# MAX490.net
KiCad netlist of a schematic drawn in Altium Designer
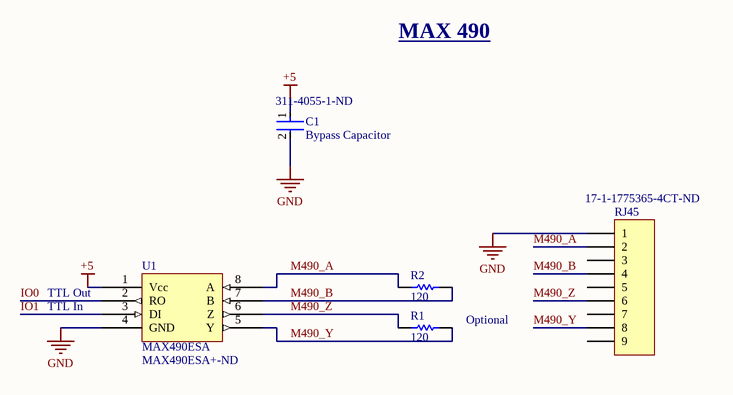
[diagram p0: MAX490.SchDoc]

(export (version "E")
  (design (tool "Eeschema 10.0.6"))
  (components
    (comp (ref "C1")
      (value "Bypass Capacitor")
      (footprint "FP-CC0603-DA-MFG")
      (description "CAP CER 0.1UF 10V X7R 0603")
      (fields
        (field (name "OCTOPART") "https://octopart.com/cc0603krx7r6bb104-yageo-9291607")
        (field (name "TOLERANCE") "0.1")
        (field (name "SUPPLIER PART NUMBER 1") "311-4055-1-ND")
      )
      (libsource (lib "Altium Content Vault") (part "11868f565c42a9108669ba33697ecf6"))
    )
    (comp (ref "R1")
      (value "Optional")
      (footprint "1608[0603]")
      (description "SMD Chip Resistor, 120 Ohm, ± 5%, 250 mW, 0603 [1608 Metric], Thick Film, Anti-Surge")
      (fields
        (field (name "ALTIUM_VALUE") "120")
        (field (name "MANUFACTURER") "Panasonic")
        (field (name "MANUFACTURER PART NUMBER") "ERJ-PA3J121V")
      )
      (libsource (lib "Miscellaneous Devices") (part "Res1"))
    )
    (comp (ref "R2")
      (value "120")
      (footprint "1608[0603]")
      (description "SMD Chip Resistor, 120 Ohm, ± 5%, 250 mW, 0603 [1608 Metric], Thick Film, Anti-Surge")
      (fields
        (field (name "MANUFACTURER") "Panasonic")
        (field (name "MANUFACTURER PART NUMBER") "ERJ-PA3J121V")
      )
      (libsource (lib "Miscellaneous Devices") (part "Res1"))
    )
    (comp (ref "RJ45")
      (value "~")
      (footprint "1-1775365-4")
      (description "Telecom and Datacom Connector")
      (fields
        (field (name "SUPPLIER PART NUMBER 1") "17-1-1775365-4CT-ND")
        (field (name "MANUFACTURER") "TE Connectivity AMP")
        (field (name "MANUFACTURER PART NUMBER") "1-1775365-4")
      )
      (libsource (lib "Miscellaneous Connectors") (part "Header 9"))
    )
    (comp (ref "U1")
      (value "MAX490ESA")
      (footprint "SO-8_L")
      (description "Line Transceiver, 1 Func, 1 Driver, 1 Rcvr, CMOS, PDSO8")
      (fields
        (field (name "MANUFACTURER") "Maxim")
        (field (name "MANUFACTURER PART NUMBER") "MAX490ESA+")
        (field (name "SUPPLIER PART NUMBER 1") "MAX490ESA+-ND")
      )
      (libsource (lib "MAX490_Corrected_Symbol") (part "MAX490ESA"))
    )
  )
  (nets
    (net (code "1") (name "+5") (class "Default")
      (node (ref "C1") (pin "1") (pinfunction "1_1") (pintype "passive"))
      (node (ref "U1") (pin "1") (pinfunction "Vcc_1") (pintype "power_in"))
    )
    (net (code "2") (name "/IO0") (class "Default")
      (node (ref "U1") (pin "2") (pinfunction "RO_2") (pintype "output"))
    )
    (net (code "3") (name "/IO1") (class "Default")
      (node (ref "U1") (pin "3") (pinfunction "DI_3") (pintype "input"))
    )
    (net (code "4") (name "/M490_A") (class "Default")
      (node (ref "R2") (pin "2") (pinfunction "2_2") (pintype "passive"))
      (node (ref "RJ45") (pin "2") (pinfunction "2_2") (pintype "passive"))
      (node (ref "U1") (pin "8") (pinfunction "A_8") (pintype "input"))
    )
    (net (code "5") (name "/M490_B") (class "Default")
      (node (ref "R2") (pin "1") (pinfunction "1_1") (pintype "passive"))
      (node (ref "RJ45") (pin "4") (pinfunction "4_4") (pintype "passive"))
      (node (ref "U1") (pin "7") (pinfunction "B_7") (pintype "input"))
    )
    (net (code "6") (name "/M490_Y") (class "Default")
      (node (ref "R1") (pin "1") (pinfunction "1_1") (pintype "passive"))
      (node (ref "RJ45") (pin "8") (pinfunction "8_8") (pintype "passive"))
      (node (ref "U1") (pin "5") (pinfunction "Y_5") (pintype "output"))
    )
    (net (code "7") (name "/M490_Z") (class "Default")
      (node (ref "R1") (pin "2") (pinfunction "2_2") (pintype "passive"))
      (node (ref "RJ45") (pin "6") (pinfunction "6_6") (pintype "passive"))
      (node (ref "U1") (pin "6") (pinfunction "Z_6") (pintype "output"))
    )
    (net (code "8") (name "GND") (class "Default")
      (node (ref "C1") (pin "2") (pinfunction "2_2") (pintype "passive"))
      (node (ref "RJ45") (pin "1") (pinfunction "1_1") (pintype "passive"))
      (node (ref "U1") (pin "4") (pinfunction "GND_4") (pintype "power_in"))
    )
    (net (code "9") (name "unconnected-(RJ45-Pad3)") (class "Default")
      (node (ref "RJ45") (pin "3") (pinfunction "3_3") (pintype "passive"))
    )
    (net (code "10") (name "unconnected-(RJ45-Pad5)") (class "Default")
      (node (ref "RJ45") (pin "5") (pinfunction "5_5") (pintype "passive"))
    )
    (net (code "11") (name "unconnected-(RJ45-Pad7)") (class "Default")
      (node (ref "RJ45") (pin "7") (pinfunction "7_7") (pintype "passive"))
    )
    (net (code "12") (name "unconnected-(RJ45-Pad9)") (class "Default")
      (node (ref "RJ45") (pin "9") (pinfunction "9_9") (pintype "passive"))
    )
  )
)
